# 2_4ghz_Receiver_Board.net
KiCad netlist of a schematic drawn in Altium Designer
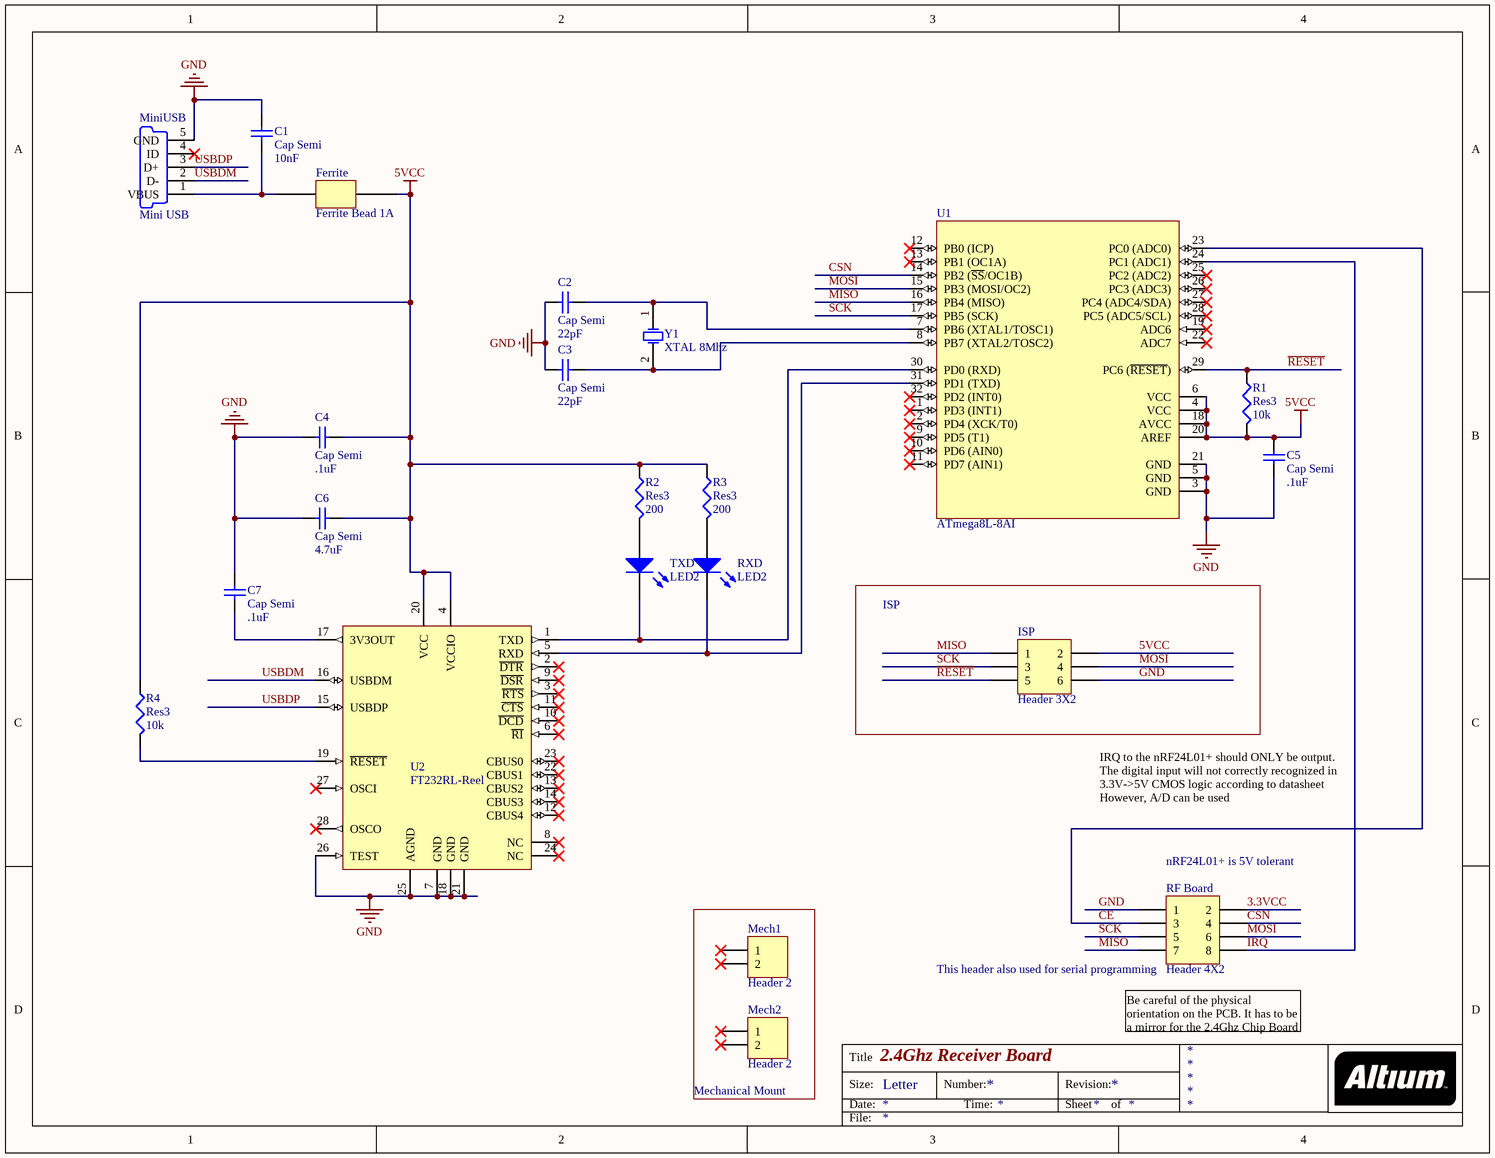
[diagram p0: 2.4ghz Receiver Board.SchDoc]

(export (version "E")
  (design (tool "Eeschema 10.0.6"))
  (components
    (comp (ref "C1")
      (value "Cap Semi")
      (footprint "CAPC2012L")
      (description "Capacitor (Semiconductor SIM Model)")
      (fields (field (name "ALTIUM_VALUE") "10nF") (field (name "PUBLISHER") "Altium Limited"))
      (libsource (lib "Miscellaneous Devices") (part "Cap Semi"))
    )
    (comp (ref "C2")
      (value "Cap Semi")
      (footprint "CAPC2012L")
      (description "Capacitor (Semiconductor SIM Model)")
      (fields (field (name "ALTIUM_VALUE") "22pF") (field (name "PUBLISHER") "Altium Limited"))
      (libsource (lib "Miscellaneous Devices") (part "Cap Semi"))
    )
    (comp (ref "C3")
      (value "Cap Semi")
      (footprint "CAPC2012L")
      (description "Capacitor (Semiconductor SIM Model)")
      (fields (field (name "ALTIUM_VALUE") "22pF") (field (name "PUBLISHER") "Altium Limited"))
      (libsource (lib "Miscellaneous Devices") (part "Cap Semi"))
    )
    (comp (ref "C4")
      (value "Cap Semi")
      (footprint "CAPC2012L")
      (description "Capacitor (Semiconductor SIM Model)")
      (fields (field (name "ALTIUM_VALUE") ".1uF") (field (name "PUBLISHER") "Altium Limited"))
      (libsource (lib "Miscellaneous Devices") (part "Cap Semi"))
    )
    (comp (ref "C5")
      (value "Cap Semi")
      (footprint "CAPC2012L")
      (description "Capacitor (Semiconductor SIM Model)")
      (fields (field (name "ALTIUM_VALUE") ".1uF") (field (name "PUBLISHER") "Altium Limited"))
      (libsource (lib "Miscellaneous Devices") (part "Cap Semi"))
    )
    (comp (ref "C6")
      (value "Cap Semi")
      (footprint "CAPC2012L")
      (description "Capacitor (Semiconductor SIM Model)")
      (fields (field (name "ALTIUM_VALUE") "4.7uF") (field (name "PUBLISHER") "Altium Limited"))
      (libsource (lib "Miscellaneous Devices") (part "Cap Semi"))
    )
    (comp (ref "C7")
      (value "Cap Semi")
      (footprint "CAPC2012L")
      (description "Capacitor (Semiconductor SIM Model)")
      (fields (field (name "ALTIUM_VALUE") ".1uF") (field (name "PUBLISHER") "Altium Limited"))
      (libsource (lib "Miscellaneous Devices") (part "Cap Semi"))
    )
    (comp (ref "Ferrite")
      (value "Ferrite Bead 1A")
      (footprint "RESC2012N")
      (libsource (lib "Ferrite Bead") (part "Ferrite Bead"))
    )
    (comp (ref "ISP")
      (value "Header 3X2")
      (footprint "HDR2X3")
      (description "Header, 3-Pin, Dual row")
      (fields (field (name "PUBLISHER") "Altium Limited"))
      (libsource (lib "Miscellaneous Connectors") (part "Header 3X2"))
    )
    (comp (ref "Mech1")
      (value "Header 2")
      (footprint "HDR1X2")
      (description "Header, 2-Pin")
      (fields (field (name "PUBLISHER") "Altium Limited"))
      (libsource (lib "Miscellaneous Connectors") (part "Header 2"))
    )
    (comp (ref "Mech2")
      (value "Header 2")
      (footprint "HDR1X2")
      (description "Header, 2-Pin")
      (fields (field (name "PUBLISHER") "Altium Limited"))
      (libsource (lib "Miscellaneous Connectors") (part "Header 2"))
    )
    (comp (ref "MiniUSB")
      (value "Mini USB")
      (footprint "MINI USB")
      (libsource (lib "Mini USB") (part "Mini USB"))
    )
    (comp (ref "R1")
      (value "Res3")
      (footprint "RESC2012N")
      (description "Resistor")
      (fields (field (name "ALTIUM_VALUE") "10k") (field (name "PUBLISHER") "Altium Limited"))
      (libsource (lib "Miscellaneous Devices") (part "Res3"))
    )
    (comp (ref "R2")
      (value "Res3")
      (footprint "RESC2012N")
      (description "Resistor")
      (fields (field (name "ALTIUM_VALUE") "200") (field (name "PUBLISHER") "Altium Limited"))
      (libsource (lib "Miscellaneous Devices") (part "Res3"))
    )
    (comp (ref "R3")
      (value "Res3")
      (footprint "RESC2012N")
      (description "Resistor")
      (fields (field (name "ALTIUM_VALUE") "200") (field (name "PUBLISHER") "Altium Limited"))
      (libsource (lib "Miscellaneous Devices") (part "Res3"))
    )
    (comp (ref "R4")
      (value "Res3")
      (footprint "RESC2012N")
      (description "Resistor")
      (fields (field (name "ALTIUM_VALUE") "10k") (field (name "PUBLISHER") "Altium Limited"))
      (libsource (lib "Miscellaneous Devices") (part "Res3"))
    )
    (comp (ref "RF Board")
      (value "Header 4X2")
      (footprint "HDR2X4")
      (description "Header, 4-Pin, Dual row")
      (fields (field (name "PUBLISHER") "Altium Limited"))
      (libsource (lib "Miscellaneous Connectors") (part "Header 4X2"))
    )
    (comp (ref "RXD")
      (value "LED2")
      (footprint "RESC3216N")
      (description "Typical RED, GREEN, YELLOW, AMBER GaAs LED")
      (fields (field (name "PUBLISHER") "Altium Limited"))
      (libsource (lib "Miscellaneous Devices") (part "LED2"))
    )
    (comp (ref "TXD")
      (value "LED2")
      (footprint "RESC1608N")
      (description "Typical RED, GREEN, YELLOW, AMBER GaAs LED")
      (fields (field (name "PUBLISHER") "Altium Limited"))
      (libsource (lib "Miscellaneous Devices") (part "LED2"))
    )
    (comp (ref "U1")
      (value "ATmega8L-8AI")
      (footprint "32A_N")
      (description "8-Bit AVR Microcontroller with 8K Bytes of In-System Programmable Flash Memory")
      (fields (field (name "PUBLISHER") "Altium Limited"))
      (libsource (lib "Atmel Microcontroller 8-Bit AVR") (part "ATmega8L-8AI"))
    )
    (comp (ref "U2")
      (value "FT232RL-Reel")
      (footprint "SSOP-28_N")
      (description "USB UART Asynchronous Serial Data Transfer Chip, SSOP-28, Tape and Reel")
      (fields (field (name "PUBLISHER") "Altium Limited"))
      (libsource (lib "FTDI Communication UART") (part "FT232RL-Reel"))
    )
    (comp (ref "Y1")
      (value "XTAL 8Mhz")
      (footprint "HC-49U - SMD")
      (description "Crystal Oscillator")
      (fields (field (name "PUBLISHER") "Altium Limited"))
      (libsource (lib "Miscellaneous Devices") (part "XTAL"))
    )
  )
  (nets
    (net (code "1") (name "/3.3VCC") (class "Default")
      (node (ref "RF Board") (pin "2") (pinfunction "2_2") (pintype "passive"))
    )
    (net (code "2") (name "/CE") (class "Default")
      (node (ref "RF Board") (pin "3") (pinfunction "3_3") (pintype "passive"))
      (node (ref "U1") (pin "23") (pinfunction "PC0_(ADC0)_23") (pintype "bidirectional"))
    )
    (net (code "3") (name "/CSN") (class "Default")
      (node (ref "RF Board") (pin "4") (pinfunction "4_4") (pintype "passive"))
      (node (ref "U1") (pin "14") (pinfunction "PB2_(~{SS}/OC1B)_14") (pintype "bidirectional"))
    )
    (net (code "4") (name "/IRQ") (class "Default")
      (node (ref "RF Board") (pin "8") (pinfunction "8_8") (pintype "passive"))
      (node (ref "U1") (pin "24") (pinfunction "PC1_(ADC1)_24") (pintype "bidirectional"))
    )
    (net (code "5") (name "/MISO") (class "Default")
      (node (ref "ISP") (pin "1") (pinfunction "1_1") (pintype "passive"))
      (node (ref "RF Board") (pin "7") (pinfunction "7_7") (pintype "passive"))
      (node (ref "U1") (pin "16") (pinfunction "PB4_(MISO)_16") (pintype "bidirectional"))
    )
    (net (code "6") (name "/MOSI") (class "Default")
      (node (ref "ISP") (pin "4") (pinfunction "4_4") (pintype "passive"))
      (node (ref "RF Board") (pin "6") (pinfunction "6_6") (pintype "passive"))
      (node (ref "U1") (pin "15") (pinfunction "PB3_(MOSI/OC2)_15") (pintype "bidirectional"))
    )
    (net (code "7") (name "/SCK") (class "Default")
      (node (ref "ISP") (pin "3") (pinfunction "3_3") (pintype "passive"))
      (node (ref "RF Board") (pin "5") (pinfunction "5_5") (pintype "passive"))
      (node (ref "U1") (pin "17") (pinfunction "PB5_(SCK)_17") (pintype "bidirectional"))
    )
    (net (code "8") (name "/USBDM") (class "Default")
      (node (ref "MiniUSB") (pin "2") (pinfunction "D-_2") (pintype "passive"))
      (node (ref "U2") (pin "16") (pinfunction "USBDM_16") (pintype "bidirectional"))
    )
    (net (code "9") (name "/USBDP") (class "Default")
      (node (ref "MiniUSB") (pin "3") (pinfunction "D+_3") (pintype "passive"))
      (node (ref "U2") (pin "15") (pinfunction "USBDP_15") (pintype "bidirectional"))
    )
    (net (code "10") (name "/~{RESET}") (class "Default")
      (node (ref "ISP") (pin "5") (pinfunction "5_5") (pintype "passive"))
      (node (ref "R1") (pin "1") (pinfunction "1_1") (pintype "passive"))
      (node (ref "U1") (pin "29") (pinfunction "PC6_(~{RESET})_29") (pintype "bidirectional"))
    )
    (net (code "11") (name "5VCC") (class "Default")
      (node (ref "C4") (pin "2") (pinfunction "2_2") (pintype "passive"))
      (node (ref "C5") (pin "2") (pinfunction "2_2") (pintype "passive"))
      (node (ref "C6") (pin "2") (pinfunction "2_2") (pintype "passive"))
      (node (ref "Ferrite") (pin "2") (pinfunction "2_2") (pintype "passive"))
      (node (ref "ISP") (pin "2") (pinfunction "2_2") (pintype "passive"))
      (node (ref "R1") (pin "2") (pinfunction "2_2") (pintype "passive"))
      (node (ref "R2") (pin "1") (pinfunction "1_1") (pintype "passive"))
      (node (ref "R3") (pin "1") (pinfunction "1_1") (pintype "passive"))
      (node (ref "R4") (pin "1") (pinfunction "1_1") (pintype "passive"))
      (node (ref "U1") (pin "18") (pinfunction "AVCC_18") (pintype "power_in"))
      (node (ref "U1") (pin "20") (pinfunction "AREF_20") (pintype "passive"))
      (node (ref "U1") (pin "4") (pinfunction "VCC_4") (pintype "power_in"))
      (node (ref "U1") (pin "6") (pinfunction "VCC_6") (pintype "power_in"))
      (node (ref "U2") (pin "20") (pinfunction "VCC_20") (pintype "power_in"))
      (node (ref "U2") (pin "4") (pinfunction "VCCIO_4") (pintype "power_in"))
    )
    (net (code "12") (name "GND") (class "Default")
      (node (ref "C1") (pin "2") (pinfunction "2_2") (pintype "passive"))
      (node (ref "C2") (pin "1") (pinfunction "1_1") (pintype "passive"))
      (node (ref "C3") (pin "1") (pinfunction "1_1") (pintype "passive"))
      (node (ref "C4") (pin "1") (pinfunction "1_1") (pintype "passive"))
      (node (ref "C5") (pin "1") (pinfunction "1_1") (pintype "passive"))
      (node (ref "C6") (pin "1") (pinfunction "1_1") (pintype "passive"))
      (node (ref "C7") (pin "2") (pinfunction "2_2") (pintype "passive"))
      (node (ref "ISP") (pin "6") (pinfunction "6_6") (pintype "passive"))
      (node (ref "MiniUSB") (pin "5") (pinfunction "GND_5") (pintype "passive"))
      (node (ref "RF Board") (pin "1") (pinfunction "1_1") (pintype "passive"))
      (node (ref "U1") (pin "21") (pinfunction "GND_21") (pintype "power_in"))
      (node (ref "U1") (pin "3") (pinfunction "GND_3") (pintype "power_in"))
      (node (ref "U1") (pin "5") (pinfunction "GND_5") (pintype "power_in"))
      (node (ref "U2") (pin "18") (pinfunction "GND_18") (pintype "power_in"))
      (node (ref "U2") (pin "21") (pinfunction "GND_21") (pintype "power_in"))
      (node (ref "U2") (pin "25") (pinfunction "AGND_25") (pintype "power_in"))
      (node (ref "U2") (pin "26") (pinfunction "TEST_26") (pintype "input"))
      (node (ref "U2") (pin "7") (pinfunction "GND_7") (pintype "power_in"))
    )
    (net (code "13") (name "Net-(MiniUSB-VBUS)") (class "Default")
      (node (ref "C1") (pin "1") (pinfunction "1_1") (pintype "passive"))
      (node (ref "Ferrite") (pin "1") (pinfunction "1_1") (pintype "passive"))
      (node (ref "MiniUSB") (pin "1") (pinfunction "VBUS_1") (pintype "passive"))
    )
    (net (code "14") (name "Net-(RXD-A)") (class "Default")
      (node (ref "R3") (pin "2") (pinfunction "2_2") (pintype "passive"))
      (node (ref "RXD") (pin "1") (pinfunction "A_1") (pintype "passive"))
    )
    (net (code "15") (name "Net-(RXD-K)") (class "Default")
      (node (ref "RXD") (pin "2") (pinfunction "K_2") (pintype "passive"))
      (node (ref "U1") (pin "31") (pinfunction "PD1_(TXD)_31") (pintype "bidirectional"))
      (node (ref "U2") (pin "5") (pinfunction "RXD_5") (pintype "input"))
    )
    (net (code "16") (name "Net-(TXD-A)") (class "Default")
      (node (ref "R2") (pin "2") (pinfunction "2_2") (pintype "passive"))
      (node (ref "TXD") (pin "1") (pinfunction "A_1") (pintype "passive"))
    )
    (net (code "17") (name "Net-(TXD-K)") (class "Default")
      (node (ref "TXD") (pin "2") (pinfunction "K_2") (pintype "passive"))
      (node (ref "U1") (pin "30") (pinfunction "PD0_(RXD)_30") (pintype "bidirectional"))
      (node (ref "U2") (pin "1") (pinfunction "TXD_1") (pintype "output"))
    )
    (net (code "18") (name "Net-(U1-PB6_(XTAL1{slash}TOSC1))") (class "Default")
      (node (ref "C2") (pin "2") (pinfunction "2_2") (pintype "passive"))
      (node (ref "U1") (pin "7") (pinfunction "PB6_(XTAL1/TOSC1)_7") (pintype "bidirectional"))
      (node (ref "Y1") (pin "1") (pinfunction "OSC1_1") (pintype "passive"))
    )
    (net (code "19") (name "Net-(U1-PB7_(XTAL2{slash}TOSC2))") (class "Default")
      (node (ref "C3") (pin "2") (pinfunction "2_2") (pintype "passive"))
      (node (ref "U1") (pin "8") (pinfunction "PB7_(XTAL2/TOSC2)_8") (pintype "bidirectional"))
      (node (ref "Y1") (pin "2") (pinfunction "OSC2_2") (pintype "passive"))
    )
    (net (code "20") (name "Net-(U2-3V3OUT)") (class "Default")
      (node (ref "C7") (pin "1") (pinfunction "1_1") (pintype "passive"))
      (node (ref "U2") (pin "17") (pinfunction "3V3OUT_17") (pintype "output"))
    )
    (net (code "21") (name "Net-(U2-~{RESET})") (class "Default")
      (node (ref "R4") (pin "2") (pinfunction "2_2") (pintype "passive"))
      (node (ref "U2") (pin "19") (pinfunction "~{RESET}_19") (pintype "input"))
    )
    (net (code "22") (name "unconnected-(Mech1-Pad1)") (class "Default")
      (node (ref "Mech1") (pin "1") (pinfunction "1_1") (pintype "passive+no_connect"))
    )
    (net (code "23") (name "unconnected-(Mech1-Pad2)") (class "Default")
      (node (ref "Mech1") (pin "2") (pinfunction "2_2") (pintype "passive+no_connect"))
    )
    (net (code "24") (name "unconnected-(Mech2-Pad1)") (class "Default")
      (node (ref "Mech2") (pin "1") (pinfunction "1_1") (pintype "passive+no_connect"))
    )
    (net (code "25") (name "unconnected-(Mech2-Pad2)") (class "Default")
      (node (ref "Mech2") (pin "2") (pinfunction "2_2") (pintype "passive+no_connect"))
    )
    (net (code "26") (name "unconnected-(MiniUSB-ID-Pad4)") (class "Default")
      (node (ref "MiniUSB") (pin "4") (pinfunction "ID_4") (pintype "passive+no_connect"))
    )
    (net (code "27") (name "unconnected-(U1-ADC6-Pad19)") (class "Default")
      (node (ref "U1") (pin "19") (pinfunction "ADC6_19") (pintype "input+no_connect"))
    )
    (net (code "28") (name "unconnected-(U1-ADC7-Pad22)") (class "Default")
      (node (ref "U1") (pin "22") (pinfunction "ADC7_22") (pintype "input+no_connect"))
    )
    (net (code "29") (name "unconnected-(U1-PB0_(ICP)-Pad12)") (class "Default")
      (node (ref "U1") (pin "12") (pinfunction "PB0_(ICP)_12") (pintype "bidirectional+no_connect"))
    )
    (net (code "30") (name "unconnected-(U1-PB1_(OC1A)-Pad13)") (class "Default")
      (node (ref "U1") (pin "13") (pinfunction "PB1_(OC1A)_13") (pintype "bidirectional+no_connect"))
    )
    (net (code "31") (name "unconnected-(U1-PC2_(ADC2)-Pad25)") (class "Default")
      (node (ref "U1") (pin "25") (pinfunction "PC2_(ADC2)_25") (pintype "bidirectional+no_connect"))
    )
    (net (code "32") (name "unconnected-(U1-PC3_(ADC3)-Pad26)") (class "Default")
      (node (ref "U1") (pin "26") (pinfunction "PC3_(ADC3)_26") (pintype "bidirectional+no_connect"))
    )
    (net (code "33") (name "unconnected-(U1-PC4_(ADC4{slash}SDA)-Pad27)") (class "Default")
      (node (ref "U1") (pin "27") (pinfunction "PC4_(ADC4/SDA)_27") (pintype "bidirectional+no_connect"))
    )
    (net (code "34") (name "unconnected-(U1-PC5_(ADC5{slash}SCL)-Pad28)") (class "Default")
      (node (ref "U1") (pin "28") (pinfunction "PC5_(ADC5/SCL)_28") (pintype "bidirectional+no_connect"))
    )
    (net (code "35") (name "unconnected-(U1-PD2_(INT0)-Pad32)") (class "Default")
      (node (ref "U1") (pin "32") (pinfunction "PD2_(INT0)_32") (pintype "bidirectional+no_connect"))
    )
    (net (code "36") (name "unconnected-(U1-PD3_(INT1)-Pad1)") (class "Default")
      (node (ref "U1") (pin "1") (pinfunction "PD3_(INT1)_1") (pintype "bidirectional+no_connect"))
    )
    (net (code "37") (name "unconnected-(U1-PD4_(XCK{slash}T0)-Pad2)") (class "Default")
      (node (ref "U1") (pin "2") (pinfunction "PD4_(XCK/T0)_2") (pintype "bidirectional+no_connect"))
    )
    (net (code "38") (name "unconnected-(U1-PD5_(T1)-Pad9)") (class "Default")
      (node (ref "U1") (pin "9") (pinfunction "PD5_(T1)_9") (pintype "bidirectional+no_connect"))
    )
    (net (code "39") (name "unconnected-(U1-PD6_(AIN0)-Pad10)") (class "Default")
      (node (ref "U1") (pin "10") (pinfunction "PD6_(AIN0)_10") (pintype "bidirectional+no_connect"))
    )
    (net (code "40") (name "unconnected-(U1-PD7_(AIN1)-Pad11)") (class "Default")
      (node (ref "U1") (pin "11") (pinfunction "PD7_(AIN1)_11") (pintype "bidirectional+no_connect"))
    )
    (net (code "41") (name "unconnected-(U2-CBUS0-Pad23)") (class "Default")
      (node (ref "U2") (pin "23") (pinfunction "CBUS0_23") (pintype "bidirectional+no_connect"))
    )
    (net (code "42") (name "unconnected-(U2-CBUS1-Pad22)") (class "Default")
      (node (ref "U2") (pin "22") (pinfunction "CBUS1_22") (pintype "bidirectional+no_connect"))
    )
    (net (code "43") (name "unconnected-(U2-CBUS2-Pad13)") (class "Default")
      (node (ref "U2") (pin "13") (pinfunction "CBUS2_13") (pintype "bidirectional+no_connect"))
    )
    (net (code "44") (name "unconnected-(U2-CBUS3-Pad14)") (class "Default")
      (node (ref "U2") (pin "14") (pinfunction "CBUS3_14") (pintype "bidirectional+no_connect"))
    )
    (net (code "45") (name "unconnected-(U2-CBUS4-Pad12)") (class "Default")
      (node (ref "U2") (pin "12") (pinfunction "CBUS4_12") (pintype "bidirectional+no_connect"))
    )
    (net (code "46") (name "unconnected-(U2-NC-Pad8)") (class "Default")
      (node (ref "U2") (pin "8") (pinfunction "NC_8") (pintype "passive+no_connect"))
    )
    (net (code "47") (name "unconnected-(U2-NC-Pad24)") (class "Default")
      (node (ref "U2") (pin "24") (pinfunction "NC_24") (pintype "passive+no_connect"))
    )
    (net (code "48") (name "unconnected-(U2-OSCI-Pad27)") (class "Default")
      (node (ref "U2") (pin "27") (pinfunction "OSCI_27") (pintype "input+no_connect"))
    )
    (net (code "49") (name "unconnected-(U2-OSCO-Pad28)") (class "Default")
      (node (ref "U2") (pin "28") (pinfunction "OSCO_28") (pintype "output+no_connect"))
    )
    (net (code "50") (name "unconnected-(U2-~{CTS}-Pad11)") (class "Default")
      (node (ref "U2") (pin "11") (pinfunction "~{CTS}_11") (pintype "input+no_connect"))
    )
    (net (code "51") (name "unconnected-(U2-~{DCD}-Pad10)") (class "Default")
      (node (ref "U2") (pin "10") (pinfunction "~{DCD}_10") (pintype "input+no_connect"))
    )
    (net (code "52") (name "unconnected-(U2-~{DSR}-Pad9)") (class "Default")
      (node (ref "U2") (pin "9") (pinfunction "~{DSR}_9") (pintype "input+no_connect"))
    )
    (net (code "53") (name "unconnected-(U2-~{DTR}-Pad2)") (class "Default")
      (node (ref "U2") (pin "2") (pinfunction "~{DTR}_2") (pintype "output+no_connect"))
    )
    (net (code "54") (name "unconnected-(U2-~{RI}-Pad6)") (class "Default")
      (node (ref "U2") (pin "6") (pinfunction "~{RI}_6") (pintype "input+no_connect"))
    )
    (net (code "55") (name "unconnected-(U2-~{RTS}-Pad3)") (class "Default")
      (node (ref "U2") (pin "3") (pinfunction "~{RTS}_3") (pintype "output+no_connect"))
    )
  )
)
